# DOAN2.net
KiCad netlist of a schematic drawn in Altium Designer
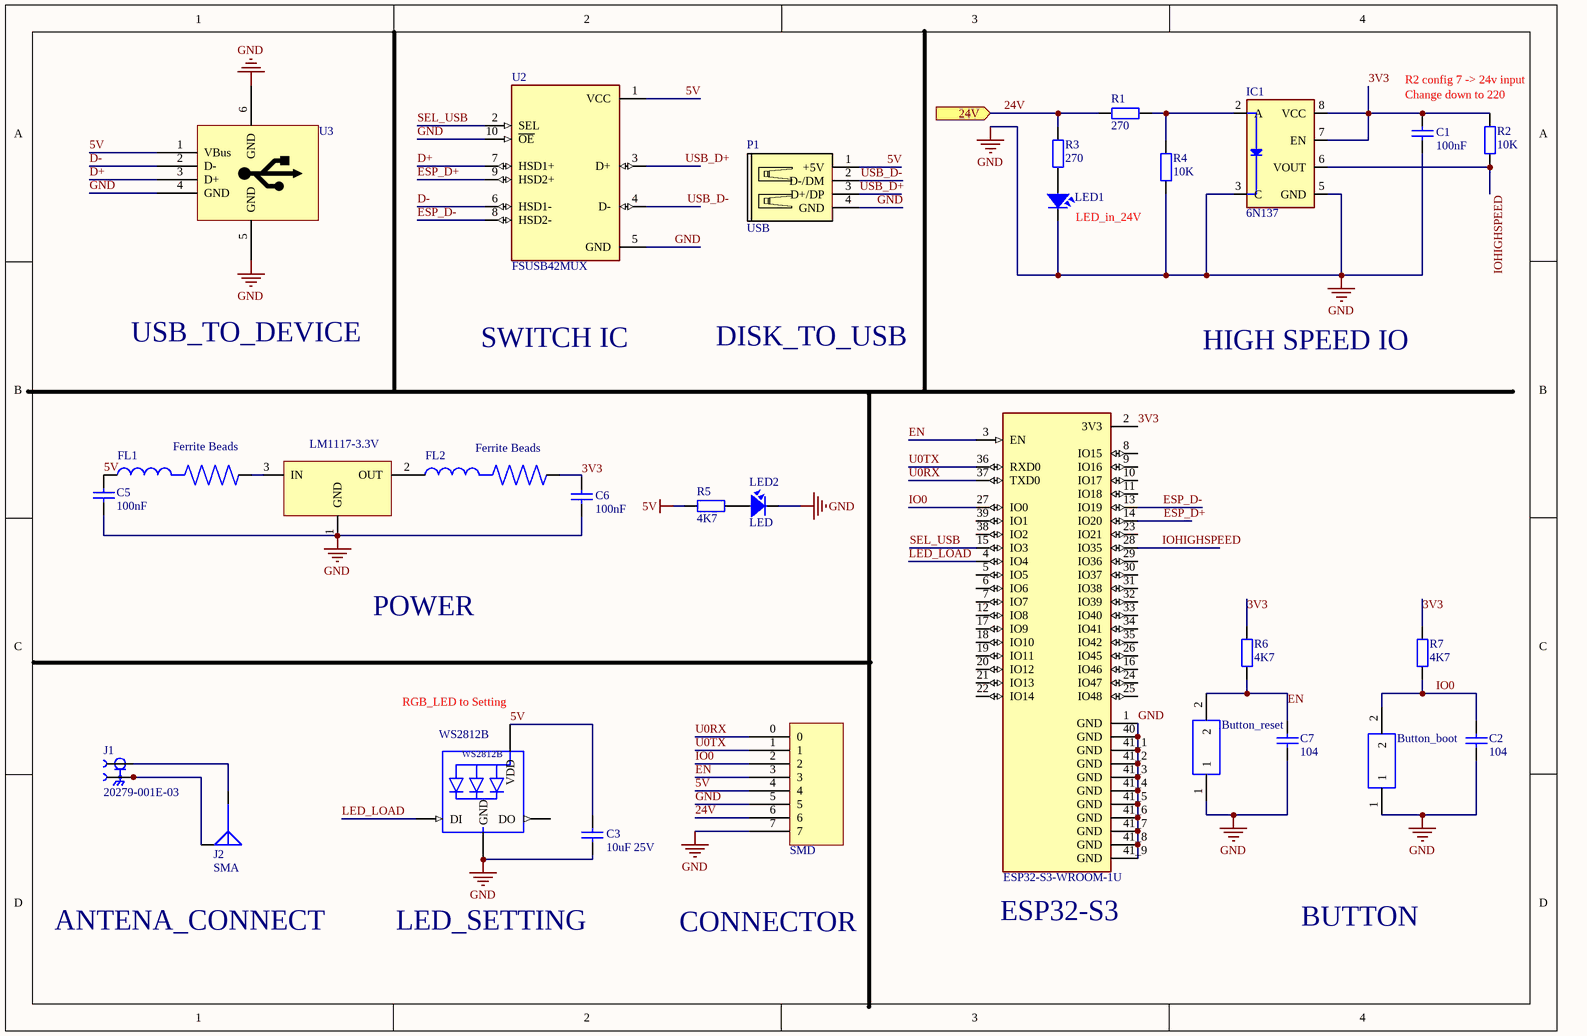
[diagram p0: DOAN2.SchDoc]

(export (version "E")
  (design (tool "Eeschema 10.0.6"))
  (components
    (comp (ref "*")
      (value "SMD")
      (footprint "PCBComponent_1")
      (libsource (lib "Connect8_SMD") (part "Component_1"))
    )
    (comp (ref "5V-3V3")
      (value "LM1117-3.3V")
      (footprint "LM1117-SOP")
      (description "800mA Low-Dropout Linear Regulator")
      (fields (field (name "CREATOR") "Nguyen Ba Bien"))
      (libsource (lib "Cty1") (part "LM1117"))
    )
    (comp (ref "Button_boot")
      (value "Component_1")
      (footprint "PCBComponent_1")
      (libsource (lib "Button_SMD") (part "Component_1"))
    )
    (comp (ref "Button_reset")
      (value "Component_1")
      (footprint "PCBComponent_1")
      (libsource (lib "Button_SMD") (part "Component_1"))
    )
    (comp (ref "C1")
      (value "100nF")
      (footprint "tu 0805")
      (description "Dán")
      (libsource (lib "Tu dien") (part "Tu 0805 104 50V 10%"))
    )
    (comp (ref "C2")
      (value "104")
      (footprint "tu 0805")
      (description "Dán")
      (libsource (lib "Tu dien") (part "Tu 0805 104 50V 10%"))
    )
    (comp (ref "C3")
      (value "10uF 25V")
      (footprint "tu 0805")
      (description "Dán")
      (libsource (lib "Tu dien") (part "Tu 0805 104 50V 10%"))
    )
    (comp (ref "C5")
      (value "100nF")
      (footprint "tu 0805")
      (description "Dán")
      (libsource (lib "Tu dien") (part "Tu 0805 104 50V 10%"))
    )
    (comp (ref "C6")
      (value "100nF")
      (footprint "tu 0805")
      (description "Dán")
      (libsource (lib "Tu dien") (part "Tu 0805 104 50V 10%"))
    )
    (comp (ref "C7")
      (value "104")
      (footprint "tu 0805")
      (description "Dán")
      (libsource (lib "Tu dien") (part "Tu 0805 104 50V 10%"))
    )
    (comp (ref "FL1")
      (value "BLM21SP111SH1D")
      (footprint "BEADC2012X105N")
      (libsource (lib "BLM21SP111SH1D") (part "BLM21SP111SH1D"))
    )
    (comp (ref "FL2")
      (value "BLM21SP111SH1D")
      (footprint "BEADC2012X105N")
      (libsource (lib "BLM21SP111SH1D") (part "BLM21SP111SH1D"))
    )
    (comp (ref "IC1")
      (value "6N137")
      (footprint "COUPL_6N138SDM")
      (libsource (lib "8SMD") (part "Component_1"))
    )
    (comp (ref "J1")
      (value "20279-001E-03")
      (footprint "IPEX_20279-001E-03")
      (fields (field (name "MF") "I-PEX"))
      (libsource (lib "20279-001E-03") (part "20279-001E-03"))
    )
    (comp (ref "J2")
      (value "SMA")
      (footprint "LINX CONREVSMA003.062")
      (libsource (lib "KhanhBK_Library_4") (part "RF Connector - SMA"))
    )
    (comp (ref "LED")
      (value "WS2812B")
      (footprint "WS2812B")
      (description "Raspberry Pi HAT _40 pin_ Wheeled Robotics Kit")
      (fields (field (name "MF") "SparkFun Electronics"))
      (libsource (lib "WS2812B") (part "WS2812B"))
    )
    (comp (ref "LED1")
      (value "LED_in_24V")
      (footprint "SM-LED-0805-Blue")
      (libsource (lib "KhanhBK_Library_4") (part "LED"))
    )
    (comp (ref "LED2")
      (value "LED")
      (footprint "SM-LED-0805-Blue")
      (libsource (lib "KhanhBK_Library_4") (part "LED"))
    )
    (comp (ref "P1")
      (value "USB")
      (footprint "USB-A-FEMALE-SMD")
      (libsource (lib "KhanhBK_Library_4") (part "USB"))
    )
    (comp (ref "R1")
      (value "270")
      (footprint "tro smd 0603")
      (description "Dán")
      (libsource (lib "Dien Tro") (part "Tro 0603 5% 1k"))
    )
    (comp (ref "R2")
      (value "10K")
      (footprint "tro smd 0603")
      (description "Dán")
      (libsource (lib "Dien Tro") (part "Tro 0603 5% 1k"))
    )
    (comp (ref "R3")
      (value "270")
      (footprint "tro smd 0603")
      (description "Dán")
      (libsource (lib "Dien Tro") (part "Tro 0603 5% 1k"))
    )
    (comp (ref "R4")
      (value "10K")
      (footprint "tro smd 0603")
      (description "Dán")
      (libsource (lib "Dien Tro") (part "Tro 0603 5% 1k"))
    )
    (comp (ref "R5")
      (value "4K7")
      (footprint "RES-SMD-0805")
      (description "Resistor R1/4W")
      (libsource (lib "KhanhBK_Library_4") (part "R"))
    )
    (comp (ref "R6")
      (value "4K7")
      (footprint "RES-SMD-0805")
      (description "Resistor R1/4W")
      (libsource (lib "KhanhBK_Library_4") (part "R"))
    )
    (comp (ref "R7")
      (value "4K7")
      (footprint "RES-SMD-0805")
      (description "Resistor R1/4W")
      (libsource (lib "KhanhBK_Library_4") (part "R"))
    )
    (comp (ref "U2")
      (value "FSUSB42MUX")
      (footprint "SOP50P490X110-10N")
      (description "FSUSB42 Series DPDT 4.3 V 480 Mbps SMT Hi Speed USB 2.0 Switch - MSOP-10")
      (fields (field (name "MF") "ON Semiconductor"))
      (libsource (lib "FSUSB42MUX") (part "FSUSB42MUX"))
    )
    (comp (ref "U3")
      (value "USB-A Through-Hole")
      (footprint "USB-A")
      (libsource (lib "Cty1") (part "USB-A TH"))
    )
    (comp (ref "U4")
      (value "ESP32-S3-WROOM-1U")
      (footprint "XCVR_ESP32-S3-WROOM-1U")
      (description "2.4 GHz Wi-Fi (802.11 b/g/n) and Bluetooth 5 (LE) module")
      (fields (field (name "MF") "Espressif Systems"))
      (libsource (lib "ESP32-S3-WROOM-1U") (part "ESP32-S3-WROOM-1U"))
    )
  )
  (nets
    (net (code "1") (name "/3V3") (class "Default")
      (node (ref "C1") (pin "1") (pinfunction "1_1") (pintype "passive"))
      (node (ref "C6") (pin "1") (pinfunction "1_1") (pintype "passive"))
      (node (ref "FL2") (pin "2") (pinfunction "2_2") (pintype "passive"))
      (node (ref "IC1") (pin "7") (pinfunction "EN_7") (pintype "bidirectional"))
      (node (ref "IC1") (pin "8") (pinfunction "VCC_8") (pintype "bidirectional"))
      (node (ref "R2") (pin "2") (pinfunction "2_2") (pintype "passive"))
      (node (ref "R6") (pin "2") (pinfunction "2_2") (pintype "passive"))
      (node (ref "R7") (pin "2") (pinfunction "2_2") (pintype "passive"))
      (node (ref "U4") (pin "2") (pinfunction "3V3_2") (pintype "power_in"))
    )
    (net (code "2") (name "/24V") (class "Default")
      (node (ref "*") (pin "6") (pinfunction "6_6") (pintype "passive"))
      (node (ref "R1") (pin "1") (pinfunction "1_1") (pintype "passive"))
      (node (ref "R3") (pin "2") (pinfunction "2_2") (pintype "passive"))
    )
    (net (code "3") (name "/D+") (class "Default")
      (node (ref "U2") (pin "7") (pinfunction "HSD1+_7") (pintype "bidirectional"))
      (node (ref "U3") (pin "3") (pinfunction "D+_3") (pintype "passive"))
    )
    (net (code "4") (name "/D-") (class "Default")
      (node (ref "U2") (pin "6") (pinfunction "HSD1-_6") (pintype "bidirectional"))
      (node (ref "U3") (pin "2") (pinfunction "D-_2") (pintype "passive"))
    )
    (net (code "5") (name "/EN") (class "Default")
      (node (ref "*") (pin "3") (pinfunction "3_3") (pintype "passive"))
      (node (ref "Button_reset") (pin "2") (pinfunction "2_2") (pintype "passive"))
      (node (ref "C7") (pin "1") (pinfunction "1_1") (pintype "passive"))
      (node (ref "R6") (pin "1") (pinfunction "1_1") (pintype "passive"))
      (node (ref "U4") (pin "3") (pinfunction "EN_3") (pintype "input"))
    )
    (net (code "6") (name "/ESP_D+") (class "Default")
      (node (ref "U2") (pin "9") (pinfunction "HSD2+_9") (pintype "bidirectional"))
      (node (ref "U4") (pin "14") (pinfunction "IO20_14") (pintype "bidirectional"))
    )
    (net (code "7") (name "/ESP_D-") (class "Default")
      (node (ref "U2") (pin "8") (pinfunction "HSD2-_8") (pintype "bidirectional"))
      (node (ref "U4") (pin "13") (pinfunction "IO19_13") (pintype "bidirectional"))
    )
    (net (code "8") (name "/IO0") (class "Default")
      (node (ref "*") (pin "2") (pinfunction "2_2") (pintype "passive"))
      (node (ref "Button_boot") (pin "2") (pinfunction "2_2") (pintype "passive"))
      (node (ref "C2") (pin "1") (pinfunction "1_1") (pintype "passive"))
      (node (ref "R7") (pin "1") (pinfunction "1_1") (pintype "passive"))
      (node (ref "U4") (pin "27") (pinfunction "IO0_27") (pintype "bidirectional"))
    )
    (net (code "9") (name "/IOHIGHSPEED") (class "Default")
      (node (ref "IC1") (pin "6") (pinfunction "VOUT_6") (pintype "bidirectional"))
      (node (ref "R2") (pin "1") (pinfunction "1_1") (pintype "passive"))
      (node (ref "U4") (pin "28") (pinfunction "IO35_28") (pintype "bidirectional"))
    )
    (net (code "10") (name "/LED_LOAD") (class "Default")
      (node (ref "LED") (pin "4-DIN") (pinfunction "DI_4-DIN") (pintype "input"))
      (node (ref "U4") (pin "4") (pinfunction "IO4_4") (pintype "bidirectional"))
    )
    (net (code "11") (name "/SEL_USB") (class "Default")
      (node (ref "U2") (pin "2") (pinfunction "SEL_2") (pintype "input"))
      (node (ref "U4") (pin "15") (pinfunction "IO3_15") (pintype "bidirectional"))
    )
    (net (code "12") (name "/U0RX") (class "Default")
      (node (ref "*") (pin "0") (pinfunction "0_0") (pintype "passive"))
      (node (ref "U4") (pin "37") (pinfunction "TXD0_37") (pintype "bidirectional"))
    )
    (net (code "13") (name "/U0TX") (class "Default")
      (node (ref "*") (pin "1") (pinfunction "1_1") (pintype "passive"))
      (node (ref "U4") (pin "36") (pinfunction "RXD0_36") (pintype "bidirectional"))
    )
    (net (code "14") (name "/USB_D+") (class "Default")
      (node (ref "P1") (pin "3") (pinfunction "D+/DP_3") (pintype "passive"))
      (node (ref "U2") (pin "3") (pinfunction "D+_3") (pintype "bidirectional"))
    )
    (net (code "15") (name "/USB_D-") (class "Default")
      (node (ref "P1") (pin "2") (pinfunction "D-/DM_2") (pintype "passive"))
      (node (ref "U2") (pin "4") (pinfunction "D-_4") (pintype "bidirectional"))
    )
    (net (code "16") (name "5V") (class "Default")
      (node (ref "*") (pin "4") (pinfunction "4_4") (pintype "passive"))
      (node (ref "C3") (pin "1") (pinfunction "1_1") (pintype "passive"))
      (node (ref "C5") (pin "1") (pinfunction "1_1") (pintype "passive"))
      (node (ref "FL1") (pin "1") (pinfunction "1_1") (pintype "passive"))
      (node (ref "LED") (pin "1-VDD") (pinfunction "VDD_1-VDD") (pintype "power_in"))
      (node (ref "P1") (pin "1") (pinfunction "+5V_1") (pintype "passive"))
      (node (ref "R5") (pin "2") (pinfunction "2_2") (pintype "passive"))
      (node (ref "U2") (pin "1") (pinfunction "VCC_1") (pintype "power_in"))
      (node (ref "U3") (pin "1") (pinfunction "VBus_1") (pintype "passive"))
    )
    (net (code "17") (name "GND") (class "Default")
      (node (ref "*") (pin "5") (pinfunction "5_5") (pintype "passive"))
      (node (ref "*") (pin "7") (pinfunction "7_7") (pintype "passive"))
      (node (ref "5V-3V3") (pin "1") (pinfunction "GND_1") (pintype "passive"))
      (node (ref "Button_boot") (pin "1") (pinfunction "1_1") (pintype "passive"))
      (node (ref "Button_reset") (pin "1") (pinfunction "1_1") (pintype "passive"))
      (node (ref "C1") (pin "2") (pinfunction "2_2") (pintype "passive"))
      (node (ref "C2") (pin "2") (pinfunction "2_2") (pintype "passive"))
      (node (ref "C3") (pin "2") (pinfunction "2_2") (pintype "passive"))
      (node (ref "C5") (pin "2") (pinfunction "2_2") (pintype "passive"))
      (node (ref "C6") (pin "2") (pinfunction "2_2") (pintype "passive"))
      (node (ref "C7") (pin "2") (pinfunction "2_2") (pintype "passive"))
      (node (ref "IC1") (pin "3") (pinfunction "C_3") (pintype "bidirectional"))
      (node (ref "IC1") (pin "5") (pinfunction "GND_5") (pintype "bidirectional"))
      (node (ref "LED") (pin "3-GND") (pinfunction "GND_3-GND") (pintype "power_in"))
      (node (ref "LED1") (pin "2") (pinfunction "2_2") (pintype "passive"))
      (node (ref "LED2") (pin "2") (pinfunction "2_2") (pintype "passive"))
      (node (ref "P1") (pin "4") (pinfunction "GND_4") (pintype "passive"))
      (node (ref "R4") (pin "1") (pinfunction "1_1") (pintype "passive"))
      (node (ref "U2") (pin "10") (pinfunction "~{OE}_10") (pintype "input"))
      (node (ref "U2") (pin "5") (pinfunction "GND_5") (pintype "power_in"))
      (node (ref "U3") (pin "4") (pinfunction "GND_4") (pintype "passive"))
      (node (ref "U3") (pin "5") (pinfunction "GND_5") (pintype "passive"))
      (node (ref "U3") (pin "6") (pinfunction "GND_6") (pintype "passive"))
      (node (ref "U4") (pin "1") (pinfunction "GND_1") (pintype "power_in"))
      (node (ref "U4") (pin "40") (pinfunction "GND_40") (pintype "power_in"))
      (node (ref "U4") (pin "41_1") (pinfunction "GND_41_1") (pintype "power_in"))
      (node (ref "U4") (pin "41_2") (pinfunction "GND_41_2") (pintype "power_in"))
      (node (ref "U4") (pin "41_3") (pinfunction "GND_41_3") (pintype "power_in"))
      (node (ref "U4") (pin "41_4") (pinfunction "GND_41_4") (pintype "power_in"))
      (node (ref "U4") (pin "41_5") (pinfunction "GND_41_5") (pintype "power_in"))
      (node (ref "U4") (pin "41_6") (pinfunction "GND_41_6") (pintype "power_in"))
      (node (ref "U4") (pin "41_7") (pinfunction "GND_41_7") (pintype "power_in"))
      (node (ref "U4") (pin "41_8") (pinfunction "GND_41_8") (pintype "power_in"))
      (node (ref "U4") (pin "41_9") (pinfunction "GND_41_9") (pintype "power_in"))
    )
    (net (code "18") (name "Net-(5V-3V3-IN)") (class "Default")
      (node (ref "5V-3V3") (pin "3") (pinfunction "IN_3") (pintype "passive"))
      (node (ref "FL1") (pin "2") (pinfunction "2_2") (pintype "passive"))
    )
    (net (code "19") (name "Net-(5V-3V3-OUT)") (class "Default")
      (node (ref "5V-3V3") (pin "2") (pinfunction "OUT_2") (pintype "passive"))
      (node (ref "FL2") (pin "1") (pinfunction "1_1") (pintype "passive"))
    )
    (net (code "20") (name "Net-(IC1-A)") (class "Default")
      (node (ref "IC1") (pin "2") (pinfunction "A_2") (pintype "bidirectional"))
      (node (ref "R1") (pin "2") (pinfunction "2_2") (pintype "passive"))
      (node (ref "R4") (pin "2") (pinfunction "2_2") (pintype "passive"))
    )
    (net (code "21") (name "Net-(J1-GROUND-Pad2)") (class "Default")
      (node (ref "J1") (pin "2") (pinfunction "GROUND_2") (pintype "passive"))
      (node (ref "J1") (pin "3") (pinfunction "GROUND_3") (pintype "passive"))
      (node (ref "J2") (pin "G") (pinfunction "G_G") (pintype "passive"))
    )
    (net (code "22") (name "Net-(J1-SIGNAL)") (class "Default")
      (node (ref "J1") (pin "1") (pinfunction "SIGNAL_1") (pintype "passive"))
      (node (ref "J2") (pin "S") (pinfunction "S_S") (pintype "passive"))
    )
    (net (code "23") (name "Net-(LED1-Pad1)") (class "Default")
      (node (ref "LED1") (pin "1") (pinfunction "1_1") (pintype "passive"))
      (node (ref "R3") (pin "1") (pinfunction "1_1") (pintype "passive"))
    )
    (net (code "24") (name "Net-(LED2-Pad1)") (class "Default")
      (node (ref "LED2") (pin "1") (pinfunction "1_1") (pintype "passive"))
      (node (ref "R5") (pin "1") (pinfunction "1_1") (pintype "passive"))
    )
    (net (code "25") (name "unconnected-(LED-DO-Pad2-DOUT)") (class "Default")
      (node (ref "LED") (pin "2-DOUT") (pinfunction "DO_2-DOUT") (pintype "output"))
    )
    (net (code "26") (name "unconnected-(U4-IO1-Pad39)") (class "Default")
      (node (ref "U4") (pin "39") (pinfunction "IO1_39") (pintype "bidirectional"))
    )
    (net (code "27") (name "unconnected-(U4-IO2-Pad38)") (class "Default")
      (node (ref "U4") (pin "38") (pinfunction "IO2_38") (pintype "bidirectional"))
    )
    (net (code "28") (name "unconnected-(U4-IO5-Pad5)") (class "Default")
      (node (ref "U4") (pin "5") (pinfunction "IO5_5") (pintype "bidirectional"))
    )
    (net (code "29") (name "unconnected-(U4-IO6-Pad6)") (class "Default")
      (node (ref "U4") (pin "6") (pinfunction "IO6_6") (pintype "bidirectional"))
    )
    (net (code "30") (name "unconnected-(U4-IO7-Pad7)") (class "Default")
      (node (ref "U4") (pin "7") (pinfunction "IO7_7") (pintype "bidirectional"))
    )
    (net (code "31") (name "unconnected-(U4-IO8-Pad12)") (class "Default")
      (node (ref "U4") (pin "12") (pinfunction "IO8_12") (pintype "bidirectional"))
    )
    (net (code "32") (name "unconnected-(U4-IO9-Pad17)") (class "Default")
      (node (ref "U4") (pin "17") (pinfunction "IO9_17") (pintype "bidirectional"))
    )
    (net (code "33") (name "unconnected-(U4-IO10-Pad18)") (class "Default")
      (node (ref "U4") (pin "18") (pinfunction "IO10_18") (pintype "bidirectional"))
    )
    (net (code "34") (name "unconnected-(U4-IO11-Pad19)") (class "Default")
      (node (ref "U4") (pin "19") (pinfunction "IO11_19") (pintype "bidirectional"))
    )
    (net (code "35") (name "unconnected-(U4-IO12-Pad20)") (class "Default")
      (node (ref "U4") (pin "20") (pinfunction "IO12_20") (pintype "bidirectional"))
    )
    (net (code "36") (name "unconnected-(U4-IO13-Pad21)") (class "Default")
      (node (ref "U4") (pin "21") (pinfunction "IO13_21") (pintype "bidirectional"))
    )
    (net (code "37") (name "unconnected-(U4-IO14-Pad22)") (class "Default")
      (node (ref "U4") (pin "22") (pinfunction "IO14_22") (pintype "bidirectional"))
    )
    (net (code "38") (name "unconnected-(U4-IO15-Pad8)") (class "Default")
      (node (ref "U4") (pin "8") (pinfunction "IO15_8") (pintype "bidirectional"))
    )
    (net (code "39") (name "unconnected-(U4-IO16-Pad9)") (class "Default")
      (node (ref "U4") (pin "9") (pinfunction "IO16_9") (pintype "bidirectional"))
    )
    (net (code "40") (name "unconnected-(U4-IO17-Pad10)") (class "Default")
      (node (ref "U4") (pin "10") (pinfunction "IO17_10") (pintype "bidirectional"))
    )
    (net (code "41") (name "unconnected-(U4-IO18-Pad11)") (class "Default")
      (node (ref "U4") (pin "11") (pinfunction "IO18_11") (pintype "bidirectional"))
    )
    (net (code "42") (name "unconnected-(U4-IO21-Pad23)") (class "Default")
      (node (ref "U4") (pin "23") (pinfunction "IO21_23") (pintype "bidirectional"))
    )
    (net (code "43") (name "unconnected-(U4-IO36-Pad29)") (class "Default")
      (node (ref "U4") (pin "29") (pinfunction "IO36_29") (pintype "bidirectional"))
    )
    (net (code "44") (name "unconnected-(U4-IO37-Pad30)") (class "Default")
      (node (ref "U4") (pin "30") (pinfunction "IO37_30") (pintype "bidirectional"))
    )
    (net (code "45") (name "unconnected-(U4-IO38-Pad31)") (class "Default")
      (node (ref "U4") (pin "31") (pinfunction "IO38_31") (pintype "bidirectional"))
    )
    (net (code "46") (name "unconnected-(U4-IO39-Pad32)") (class "Default")
      (node (ref "U4") (pin "32") (pinfunction "IO39_32") (pintype "bidirectional"))
    )
    (net (code "47") (name "unconnected-(U4-IO40-Pad33)") (class "Default")
      (node (ref "U4") (pin "33") (pinfunction "IO40_33") (pintype "bidirectional"))
    )
    (net (code "48") (name "unconnected-(U4-IO41-Pad34)") (class "Default")
      (node (ref "U4") (pin "34") (pinfunction "IO41_34") (pintype "bidirectional"))
    )
    (net (code "49") (name "unconnected-(U4-IO42-Pad35)") (class "Default")
      (node (ref "U4") (pin "35") (pinfunction "IO42_35") (pintype "bidirectional"))
    )
    (net (code "50") (name "unconnected-(U4-IO45-Pad26)") (class "Default")
      (node (ref "U4") (pin "26") (pinfunction "IO45_26") (pintype "bidirectional"))
    )
    (net (code "51") (name "unconnected-(U4-IO46-Pad16)") (class "Default")
      (node (ref "U4") (pin "16") (pinfunction "IO46_16") (pintype "bidirectional"))
    )
    (net (code "52") (name "unconnected-(U4-IO47-Pad24)") (class "Default")
      (node (ref "U4") (pin "24") (pinfunction "IO47_24") (pintype "bidirectional"))
    )
    (net (code "53") (name "unconnected-(U4-IO48-Pad25)") (class "Default")
      (node (ref "U4") (pin "25") (pinfunction "IO48_25") (pintype "bidirectional"))
    )
  )
)
